# ProPrj_esp32s3-ai-chat_audio_2024-09-03.net
KiCad netlist of a schematic drawn in EasyEDA Pro
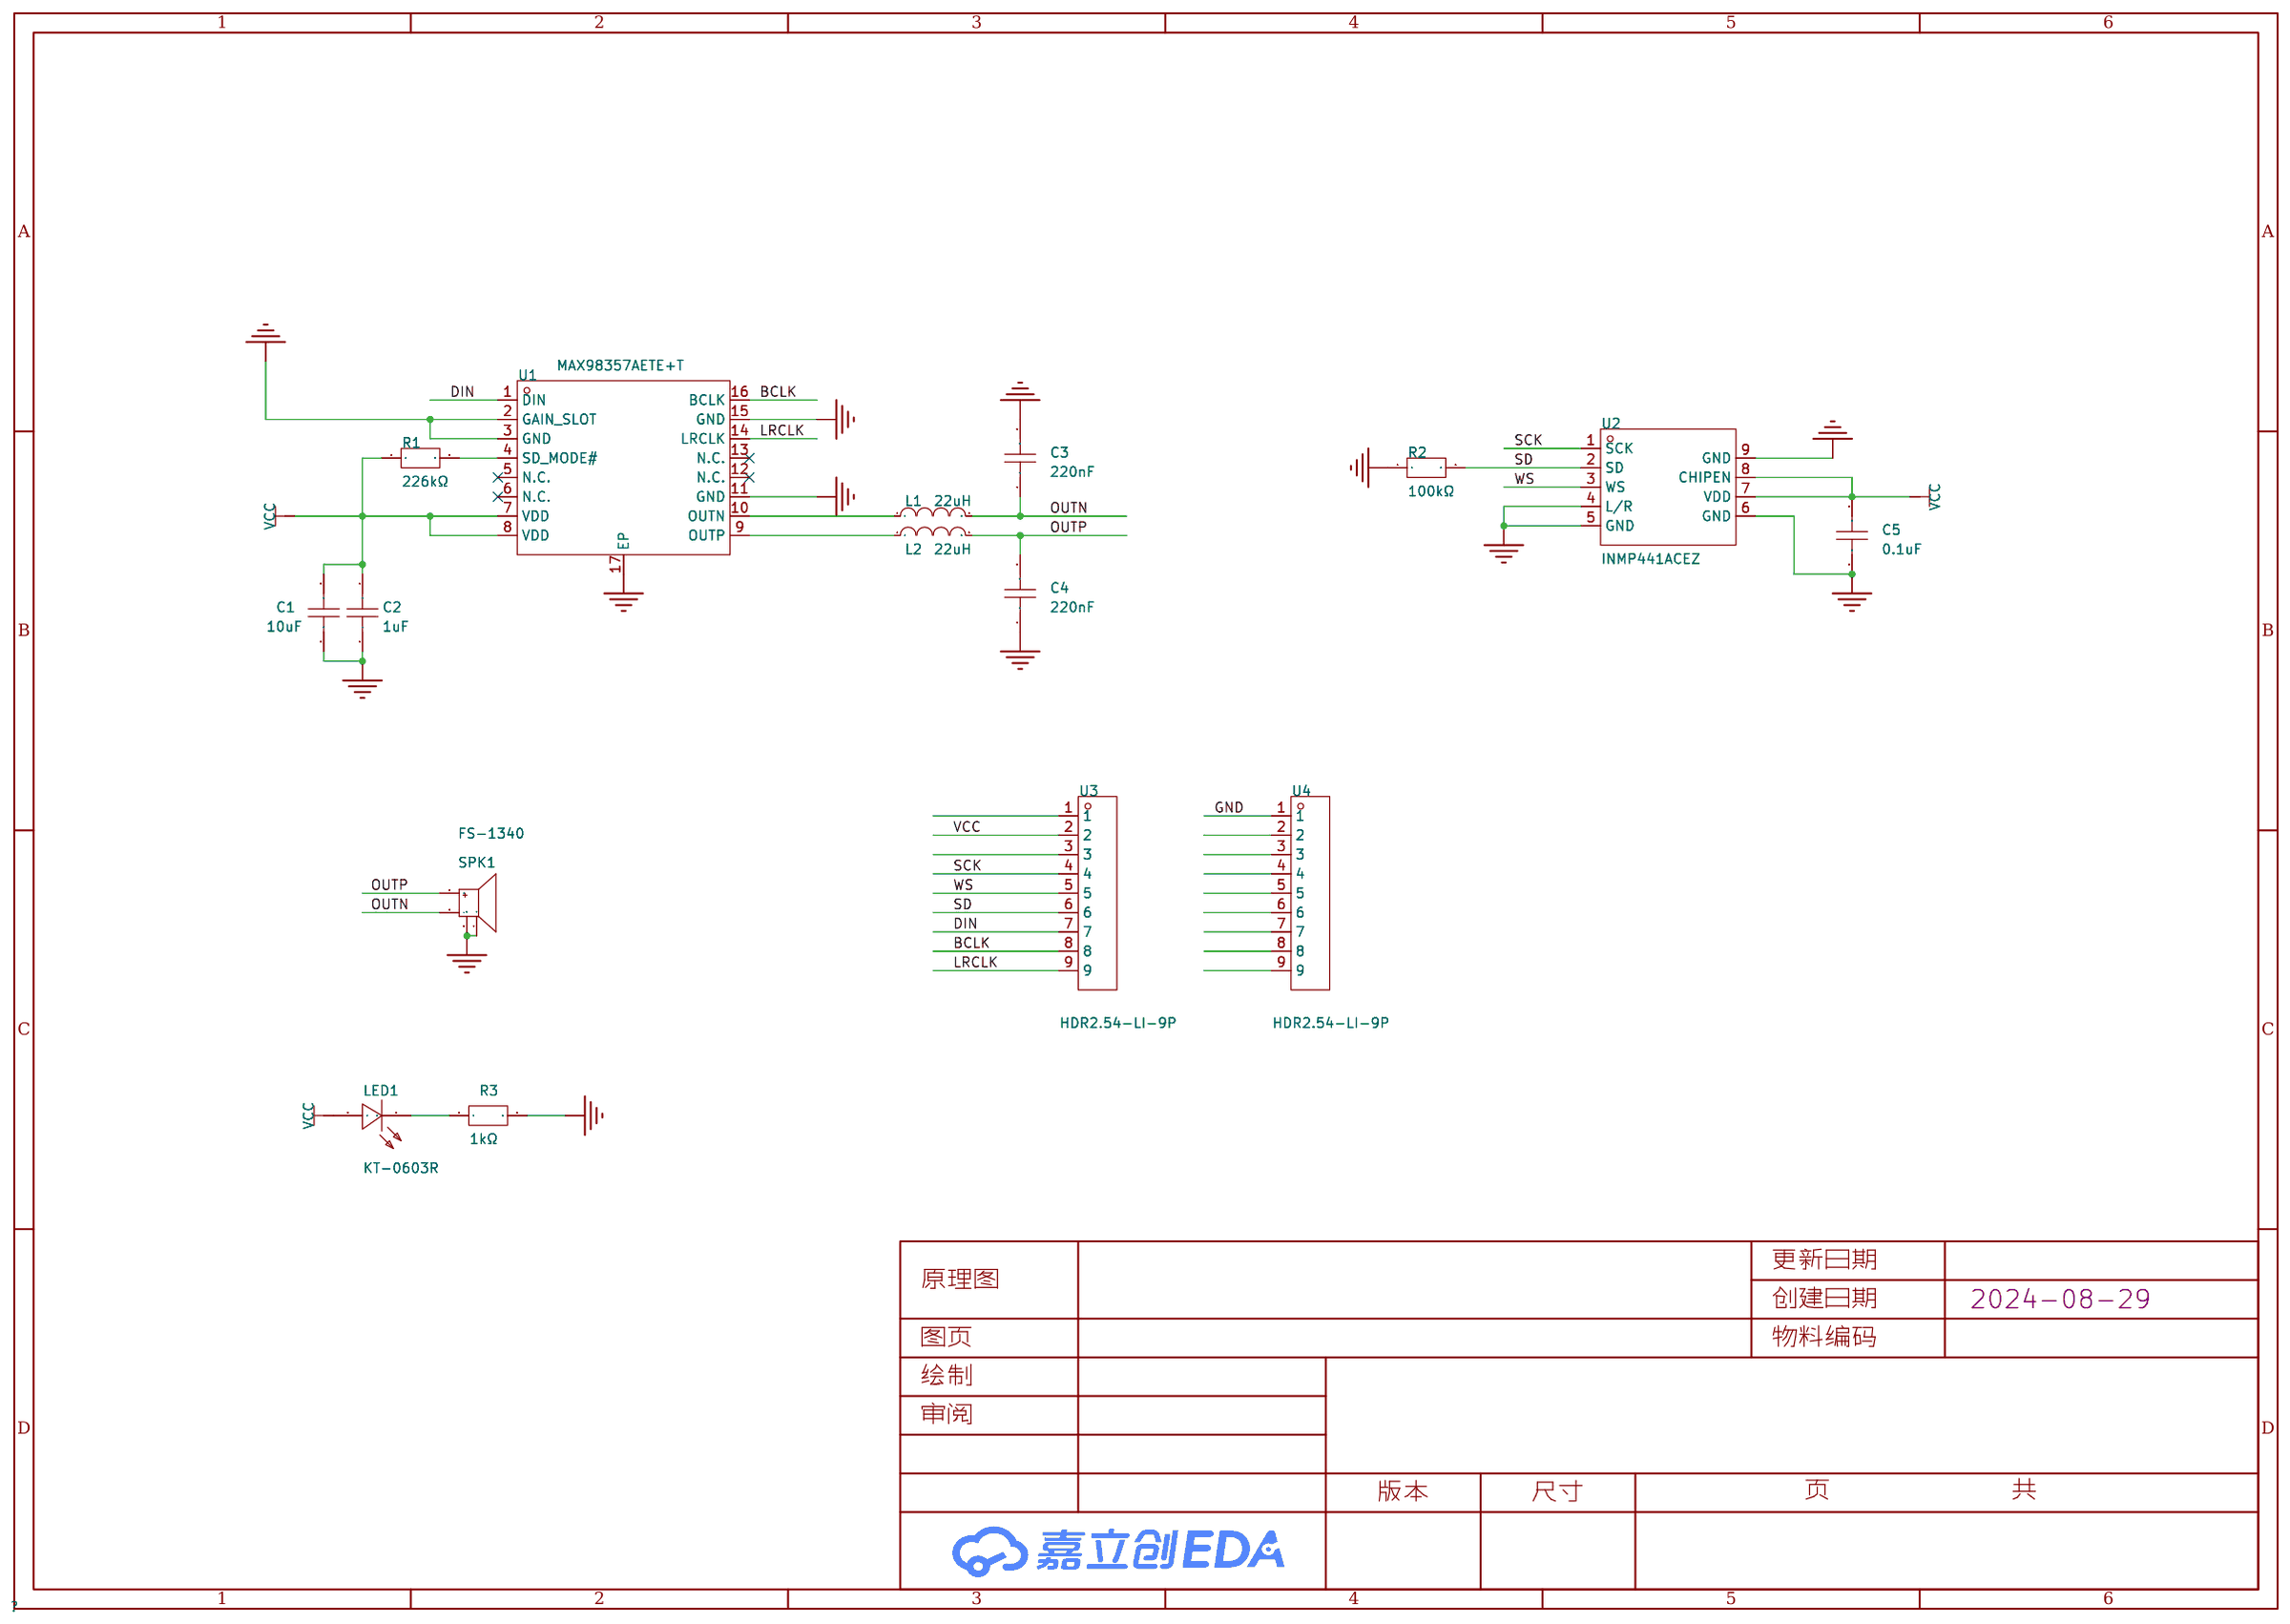
[diagram p0: schematic sheet]

(export (version "E")
  (design (tool "Eeschema 10.0.6"))
  (components
    (comp (ref "C1")
      (value "10uF")
      (footprint "easyedapro:C0603")
      (description "容值:10uF;精度:±20%;额定电压:10V;材质(温度系数):X6S;")
      (fields
        (field (name "Manufacturer Part") "GRT188C81A106ME13J")
        (field (name "Manufacturer") "muRata(村田)")
      )
      (libsource (lib "easyedapro") (part "GRT188C81A106ME13J"))
    )
    (comp (ref "C2")
      (value "1uF")
      (footprint "easyedapro:C0603")
      (description "容值:10uF;精度:±20%;额定电压:10V;材质(温度系数):X6S;")
      (fields
        (field (name "Manufacturer Part") "GRT188C81A106ME13J")
        (field (name "Manufacturer") "muRata(村田)")
      )
      (libsource (lib "easyedapro") (part "GRT188C81A106ME13J"))
    )
    (comp (ref "C3")
      (value "220nF")
      (footprint "easyedapro:C0603")
      (description "容值:10uF;精度:±20%;额定电压:10V;材质(温度系数):X6S;")
      (fields
        (field (name "Manufacturer Part") "GRT188C81A106ME13J")
        (field (name "Manufacturer") "muRata(村田)")
      )
      (libsource (lib "easyedapro") (part "GRT188C81A106ME13J"))
    )
    (comp (ref "C4")
      (value "220nF")
      (footprint "easyedapro:C0603")
      (description "容值:10uF;精度:±20%;额定电压:10V;材质(温度系数):X6S;")
      (fields
        (field (name "Manufacturer Part") "GRT188C81A106ME13J")
        (field (name "Manufacturer") "muRata(村田)")
      )
      (libsource (lib "easyedapro") (part "GRT188C81A106ME13J"))
    )
    (comp (ref "C5")
      (value "0.1uF")
      (footprint "easyedapro:C0603")
      (description "容值:10uF;精度:±20%;额定电压:10V;材质(温度系数):X6S;")
      (fields
        (field (name "Manufacturer Part") "GRT188C81A106ME13J")
        (field (name "Manufacturer") "muRata(村田)")
      )
      (libsource (lib "easyedapro") (part "GRT188C81A106ME13J"))
    )
    (comp (ref "L1")
      (value "22uH")
      (footprint "easyedapro:L0603")
      (description "电感值:22uH;精度:±20%;额定电流:2mA;饱和电流(Isat):-;直流电阻(DCR):1.7Ω;")
      (fields (field (name "Manufacturer Part") "MLF1608C220M") (field (name "Manufacturer") "TDK"))
      (libsource (lib "easyedapro") (part "MLF1608C220M"))
    )
    (comp (ref "L2")
      (value "22uH")
      (footprint "easyedapro:L0603")
      (description "电感值:22uH;精度:±20%;额定电流:2mA;饱和电流(Isat):-;直流电阻(DCR):1.7Ω;")
      (fields (field (name "Manufacturer Part") "MLF1608C220M") (field (name "Manufacturer") "TDK"))
      (libsource (lib "easyedapro") (part "MLF1608C220M"))
    )
    (comp (ref "LED1")
      (value "KT-0603R")
      (footprint "easyedapro:LED0603-RD")
      (description "发光颜色:红色;功率:-;正向电流:-;主波长:-;二极管配置:-;透镜颜色:-;色温:-;发光角度:-;载带方式:-;工作温度:-40°C~+85°C;")
      (fields (field (name "Manufacturer") "KENTO"))
      (libsource (lib "easyedapro") (part "KT-0603R"))
    )
    (comp (ref "R1")
      (value "226kΩ")
      (footprint "easyedapro:R0603")
      (description "电阻类型:-;阻值:100kΩ;精度:±5%;功率:200mW;最大工作电压:75V;温度系数:±100ppm/°C;")
      (fields
        (field (name "Manufacturer Part") "HQ03W5J0104T5E")
        (field (name "Manufacturer") "UNI-ROYAL(厚声)")
      )
      (libsource (lib "easyedapro") (part "HQ03W5J0104T5E"))
    )
    (comp (ref "R2")
      (value "100kΩ")
      (footprint "easyedapro:R0603")
      (description "电阻类型:-;阻值:100kΩ;精度:±5%;功率:200mW;最大工作电压:75V;温度系数:±100ppm/°C;")
      (fields
        (field (name "Manufacturer Part") "HQ03W5J0104T5E")
        (field (name "Manufacturer") "UNI-ROYAL(厚声)")
      )
      (libsource (lib "easyedapro") (part "HQ03W5J0104T5E"))
    )
    (comp (ref "R3")
      (value "1kΩ")
      (footprint "easyedapro:R0603")
      (description "电阻类型:-;阻值:100kΩ;精度:±5%;功率:200mW;最大工作电压:75V;温度系数:±100ppm/°C;")
      (fields
        (field (name "Manufacturer Part") "HQ03W5J0104T5E")
        (field (name "Manufacturer") "UNI-ROYAL(厚声)")
      )
      (libsource (lib "easyedapro") (part "HQ03W5J0104T5E"))
    )
    (comp (ref "SPK1")
      (value "FS-1340")
      (footprint "easyedapro:BUZ-SMD_4P-L13.0-W13.0-P11.4-BL")
      (fields (field (name "Manufacturer") "FUET(福声科技)"))
      (libsource (lib "easyedapro") (part "FS-1340"))
    )
    (comp (ref "U1")
      (value "MAX98357AETE+T")
      (footprint "easyedapro:TQFN-16_L3.0-W3.0-P0.50-BL-EP1.5")
      (description "功放类型:-;扬声器通道数:单声道;输出功率:3.2Wx2@4Ω;")
      (fields (field (name "Manufacturer") "ADI(亚德诺)/MAXIM(美信)"))
      (libsource (lib "easyedapro") (part "MAX98357AETE+T"))
    )
    (comp (ref "U2")
      (value "INMP441ACEZ")
      (footprint "easyedapro:MID-SMD_L4.7-W3.8_INMP441ACEZ")
      (libsource (lib "easyedapro") (part "INMP441ACEZ"))
    )
    (comp (ref "U3")
      (value "HDR2.54-LI-9P")
      (footprint "easyedapro:HDR-TH_9P-P2.54-V-M")
      (libsource (lib "easyedapro") (part "HDR2.54-LI-9P"))
    )
    (comp (ref "U4")
      (value "HDR2.54-LI-9P")
      (footprint "easyedapro:HDR-TH_9P-P2.54-V-M")
      (libsource (lib "easyedapro") (part "HDR2.54-LI-9P"))
    )
  )
  (nets
    (net (code "1") (name "/BCLK") (class "Default")
      (node (ref "U1") (pin "16") (pinfunction "BCLK_16") (pintype "unspecified"))
      (node (ref "U3") (pin "8") (pinfunction "8_8") (pintype "unspecified"))
    )
    (net (code "2") (name "/DIN") (class "Default")
      (node (ref "U1") (pin "1") (pinfunction "DIN_1") (pintype "unspecified"))
      (node (ref "U3") (pin "7") (pinfunction "7_7") (pintype "unspecified"))
    )
    (net (code "3") (name "/LRCLK") (class "Default")
      (node (ref "U1") (pin "14") (pinfunction "LRCLK_14") (pintype "unspecified"))
      (node (ref "U3") (pin "9") (pinfunction "9_9") (pintype "unspecified"))
    )
    (net (code "4") (name "/OUTN") (class "Default")
      (node (ref "C3") (pin "1") (pinfunction "1_1") (pintype "unspecified"))
      (node (ref "L1") (pin "2") (pinfunction "2_2") (pintype "unspecified"))
      (node (ref "SPK1") (pin "2") (pinfunction "-_2") (pintype "input"))
    )
    (net (code "5") (name "/OUTP") (class "Default")
      (node (ref "C4") (pin "2") (pinfunction "2_2") (pintype "unspecified"))
      (node (ref "L2") (pin "2") (pinfunction "2_2") (pintype "unspecified"))
      (node (ref "SPK1") (pin "1") (pinfunction "+_1") (pintype "input"))
    )
    (net (code "6") (name "/SCK") (class "Default")
      (node (ref "U2") (pin "1") (pinfunction "SCK_1") (pintype "unspecified"))
      (node (ref "U3") (pin "4") (pinfunction "4_4") (pintype "unspecified"))
    )
    (net (code "7") (name "/SD") (class "Default")
      (node (ref "R2") (pin "2") (pinfunction "2_2") (pintype "unspecified"))
      (node (ref "U2") (pin "2") (pinfunction "SD_2") (pintype "unspecified"))
      (node (ref "U3") (pin "6") (pinfunction "6_6") (pintype "unspecified"))
    )
    (net (code "8") (name "/WS") (class "Default")
      (node (ref "U2") (pin "3") (pinfunction "WS_3") (pintype "unspecified"))
      (node (ref "U3") (pin "5") (pinfunction "5_5") (pintype "unspecified"))
    )
    (net (code "9") (name "GND") (class "Default")
      (node (ref "C1") (pin "1") (pinfunction "1_1") (pintype "unspecified"))
      (node (ref "C2") (pin "1") (pinfunction "1_1") (pintype "unspecified"))
      (node (ref "C3") (pin "2") (pinfunction "2_2") (pintype "unspecified"))
      (node (ref "C4") (pin "1") (pinfunction "1_1") (pintype "unspecified"))
      (node (ref "C5") (pin "1") (pinfunction "1_1") (pintype "unspecified"))
      (node (ref "R2") (pin "1") (pinfunction "1_1") (pintype "unspecified"))
      (node (ref "R3") (pin "2") (pinfunction "2_2") (pintype "unspecified"))
      (node (ref "SPK1") (pin "3") (pinfunction "3_3") (pintype "input"))
      (node (ref "SPK1") (pin "4") (pinfunction "4_4") (pintype "input"))
      (node (ref "U1") (pin "11") (pinfunction "GND_11") (pintype "unspecified"))
      (node (ref "U1") (pin "15") (pinfunction "GND_15") (pintype "unspecified"))
      (node (ref "U1") (pin "17") (pinfunction "EP_17") (pintype "unspecified"))
      (node (ref "U1") (pin "2") (pinfunction "GAIN_SLOT_2") (pintype "unspecified"))
      (node (ref "U1") (pin "3") (pinfunction "GND_3") (pintype "unspecified"))
      (node (ref "U2") (pin "4") (pinfunction "L/R_4") (pintype "unspecified"))
      (node (ref "U2") (pin "5") (pinfunction "GND_5") (pintype "unspecified"))
      (node (ref "U2") (pin "6") (pinfunction "GND_6") (pintype "unspecified"))
      (node (ref "U2") (pin "9") (pinfunction "GND_9") (pintype "unspecified"))
      (node (ref "U4") (pin "1") (pinfunction "1_1") (pintype "unspecified"))
    )
    (net (code "10") (name "Net-(LED1-K)") (class "Default")
      (node (ref "LED1") (pin "1") (pinfunction "K_1") (pintype "input"))
      (node (ref "R3") (pin "1") (pinfunction "1_1") (pintype "unspecified"))
    )
    (net (code "11") (name "Net-(U1-OUTN)") (class "Default")
      (node (ref "L1") (pin "1") (pinfunction "1_1") (pintype "unspecified"))
      (node (ref "U1") (pin "10") (pinfunction "OUTN_10") (pintype "unspecified"))
    )
    (net (code "12") (name "Net-(U1-OUTP)") (class "Default")
      (node (ref "L2") (pin "1") (pinfunction "1_1") (pintype "unspecified"))
      (node (ref "U1") (pin "9") (pinfunction "OUTP_9") (pintype "unspecified"))
    )
    (net (code "13") (name "Net-(U1-SD_MODE#)") (class "Default")
      (node (ref "R1") (pin "2") (pinfunction "2_2") (pintype "unspecified"))
      (node (ref "U1") (pin "4") (pinfunction "SD_MODE#_4") (pintype "unspecified"))
    )
    (net (code "14") (name "VCC") (class "Default")
      (node (ref "C1") (pin "2") (pinfunction "2_2") (pintype "unspecified"))
      (node (ref "C2") (pin "2") (pinfunction "2_2") (pintype "unspecified"))
      (node (ref "C5") (pin "2") (pinfunction "2_2") (pintype "unspecified"))
      (node (ref "LED1") (pin "2") (pinfunction "A_2") (pintype "input"))
      (node (ref "R1") (pin "1") (pinfunction "1_1") (pintype "unspecified"))
      (node (ref "U1") (pin "7") (pinfunction "VDD_7") (pintype "unspecified"))
      (node (ref "U1") (pin "8") (pinfunction "VDD_8") (pintype "unspecified"))
      (node (ref "U2") (pin "7") (pinfunction "VDD_7") (pintype "unspecified"))
      (node (ref "U2") (pin "8") (pinfunction "CHIPEN_8") (pintype "unspecified"))
      (node (ref "U3") (pin "2") (pinfunction "2_2") (pintype "unspecified"))
    )
    (net (code "15") (name "unconnected-(U1-N.C.-Pad5)") (class "Default")
      (node (ref "U1") (pin "5") (pinfunction "N.C._5") (pintype "unspecified+no_connect"))
    )
    (net (code "16") (name "unconnected-(U1-N.C.-Pad6)") (class "Default")
      (node (ref "U1") (pin "6") (pinfunction "N.C._6") (pintype "unspecified+no_connect"))
    )
    (net (code "17") (name "unconnected-(U1-N.C.-Pad12)") (class "Default")
      (node (ref "U1") (pin "12") (pinfunction "N.C._12") (pintype "unspecified+no_connect"))
    )
    (net (code "18") (name "unconnected-(U1-N.C.-Pad13)") (class "Default")
      (node (ref "U1") (pin "13") (pinfunction "N.C._13") (pintype "unspecified+no_connect"))
    )
    (net (code "19") (name "unconnected-(U3-Pad1)") (class "Default")
      (node (ref "U3") (pin "1") (pinfunction "1_1") (pintype "unspecified"))
    )
    (net (code "20") (name "unconnected-(U3-Pad3)") (class "Default")
      (node (ref "U3") (pin "3") (pinfunction "3_3") (pintype "unspecified"))
    )
    (net (code "21") (name "unconnected-(U4-Pad2)") (class "Default")
      (node (ref "U4") (pin "2") (pinfunction "2_2") (pintype "unspecified"))
    )
    (net (code "22") (name "unconnected-(U4-Pad3)") (class "Default")
      (node (ref "U4") (pin "3") (pinfunction "3_3") (pintype "unspecified"))
    )
    (net (code "23") (name "unconnected-(U4-Pad4)") (class "Default")
      (node (ref "U4") (pin "4") (pinfunction "4_4") (pintype "unspecified"))
    )
    (net (code "24") (name "unconnected-(U4-Pad5)") (class "Default")
      (node (ref "U4") (pin "5") (pinfunction "5_5") (pintype "unspecified"))
    )
    (net (code "25") (name "unconnected-(U4-Pad6)") (class "Default")
      (node (ref "U4") (pin "6") (pinfunction "6_6") (pintype "unspecified"))
    )
    (net (code "26") (name "unconnected-(U4-Pad7)") (class "Default")
      (node (ref "U4") (pin "7") (pinfunction "7_7") (pintype "unspecified"))
    )
    (net (code "27") (name "unconnected-(U4-Pad8)") (class "Default")
      (node (ref "U4") (pin "8") (pinfunction "8_8") (pintype "unspecified"))
    )
    (net (code "28") (name "unconnected-(U4-Pad9)") (class "Default")
      (node (ref "U4") (pin "9") (pinfunction "9_9") (pintype "unspecified"))
    )
  )
)
